# SparkFun_ZOE-M8Q_GPS.net
KiCad netlist of a schematic drawn in EAGLE
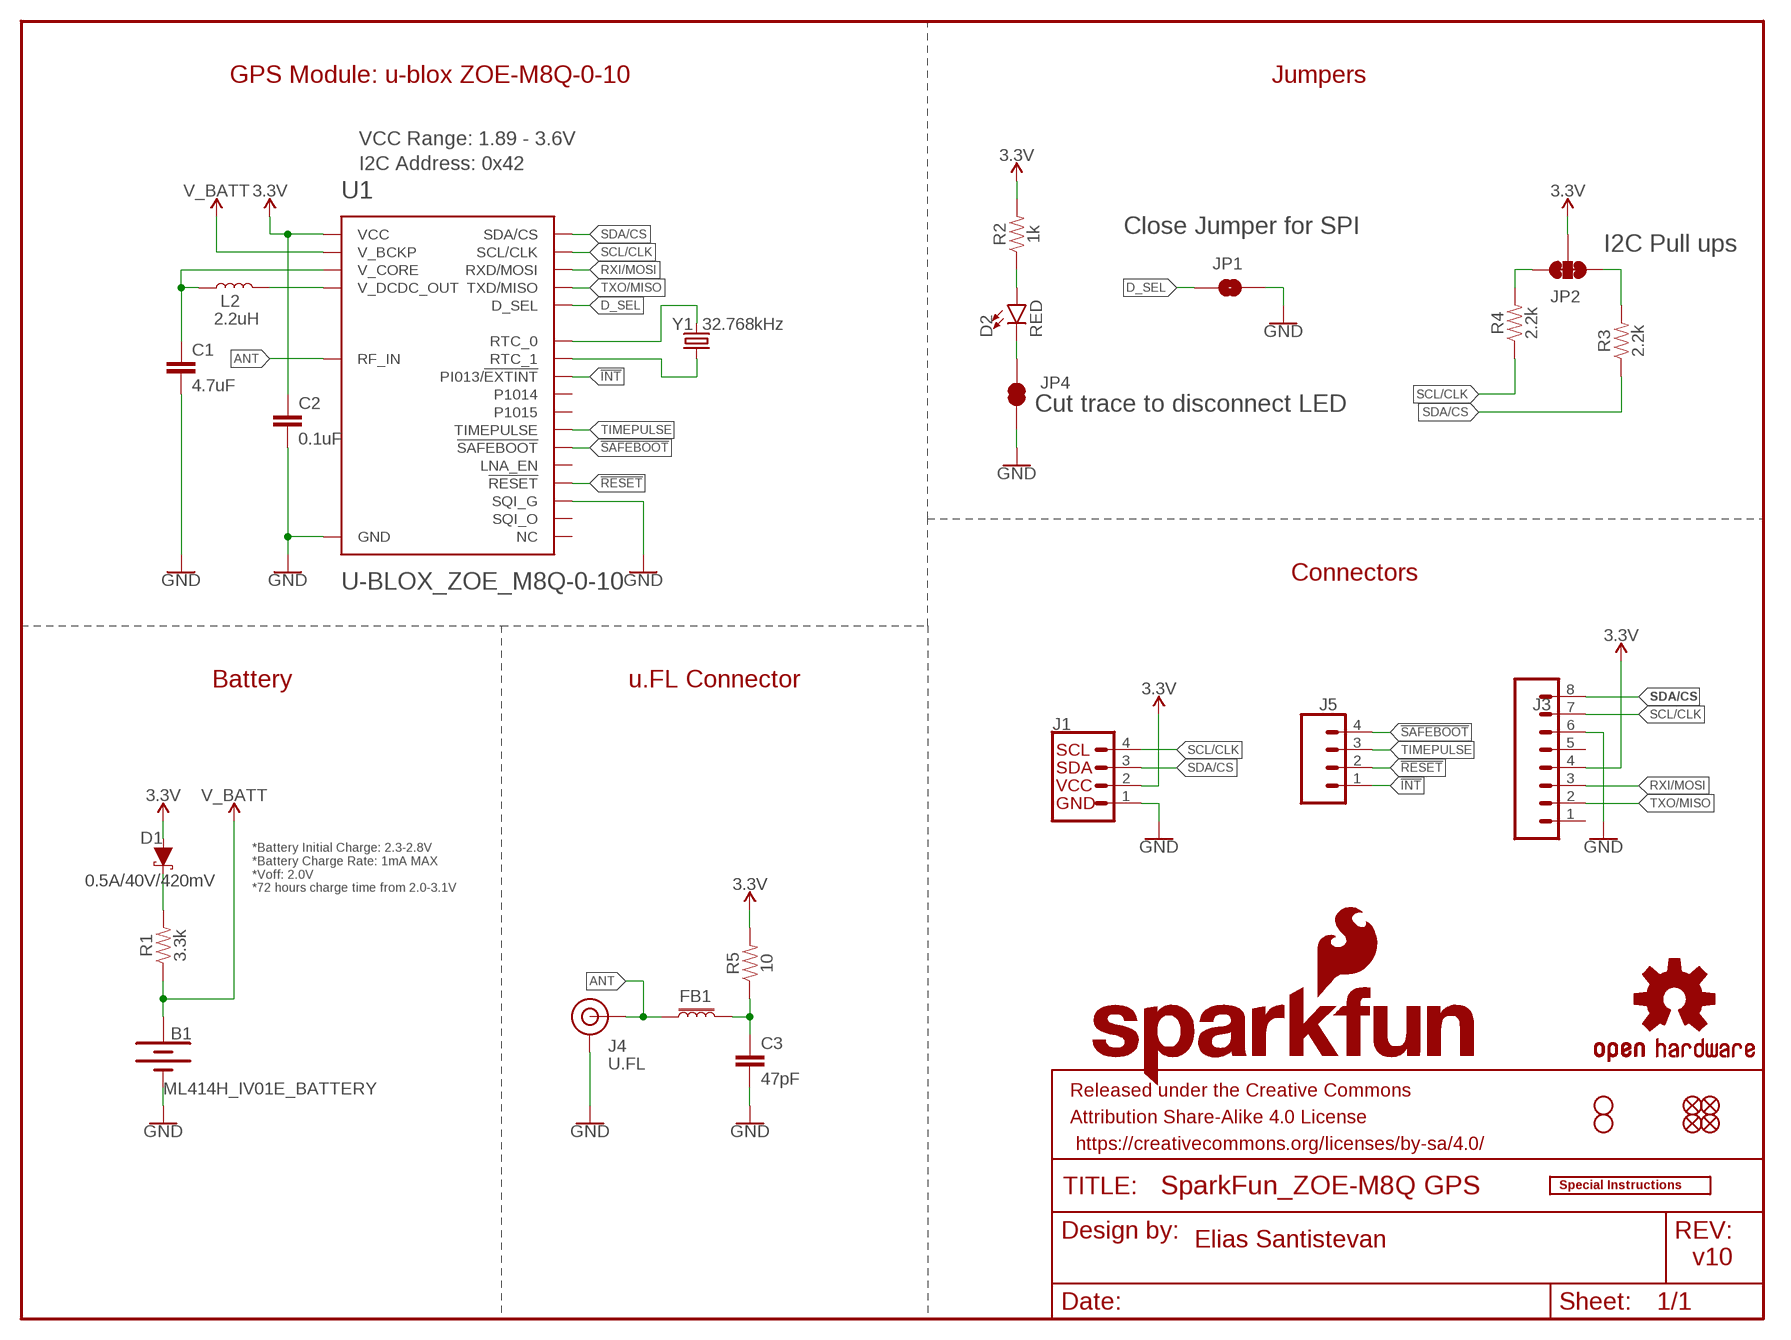
[diagram p0: schematic, sheet 1]

(export (version "E")
  (design (tool "Eeschema 10.0.6"))
  (components
    (comp (ref "B1")
      (value "ML414H_IV01E_BATTERY")
      (footprint "eagle-import:ML414H_IV01E")
      (libsource (lib "eagle-import") (part "ML414H_IV01E_BATTERY"))
    )
    (comp (ref "C1")
      (value "4.7uF")
      (footprint "eagle-import:0603")
      (libsource (lib "eagle-import") (part "4.7UF-0603-6.3V-(10%)"))
    )
    (comp (ref "C2")
      (value "0.1uF")
      (footprint "eagle-import:0603")
      (libsource (lib "eagle-import") (part "0.1UF-0603-25V-(+80/-20%)"))
    )
    (comp (ref "C3")
      (value "47pF")
      (footprint "eagle-import:0603")
      (libsource (lib "eagle-import") (part "47PF-0603-50V-5%"))
    )
    (comp (ref "D1")
      (value "0.5A/40V/420mV")
      (footprint "eagle-import:SOD-323")
      (libsource (lib "eagle-import") (part "DIODE-SCHOTTKY-PMEG4005EJ"))
    )
    (comp (ref "D2")
      (value "RED")
      (footprint "eagle-import:LED-0603")
      (libsource (lib "eagle-import") (part "LED-RED0603"))
    )
    (comp (ref "FB1")
      (value "FERRITE_BEAD-120_OHM-0402")
      (footprint "eagle-import:0402")
      (fields (field (name "MFG_PART") "BLM15HB121SN1D"))
      (libsource (lib "eagle-import") (part "FERRITE_BEAD-120_OHM-0402"))
    )
    (comp (ref "FD1")
      (value "FIDUCIALUFIDUCIAL")
      (footprint "eagle-import:FIDUCIAL-MICRO")
      (libsource (lib "eagle-import") (part "FIDUCIALUFIDUCIAL"))
    )
    (comp (ref "FD2")
      (value "FIDUCIALUFIDUCIAL")
      (footprint "eagle-import:FIDUCIAL-MICRO")
      (libsource (lib "eagle-import") (part "FIDUCIALUFIDUCIAL"))
    )
    (comp (ref "FD3")
      (value "FIDUCIALUFIDUCIAL")
      (footprint "eagle-import:FIDUCIAL-MICRO")
      (libsource (lib "eagle-import") (part "FIDUCIALUFIDUCIAL"))
    )
    (comp (ref "FD4")
      (value "FIDUCIALUFIDUCIAL")
      (footprint "eagle-import:FIDUCIAL-MICRO")
      (libsource (lib "eagle-import") (part "FIDUCIALUFIDUCIAL"))
    )
    (comp (ref "FRAME1")
      (value "FRAME-LETTER")
      (footprint "eagle-import:CREATIVE_COMMONS")
      (libsource (lib "eagle-import") (part "FRAME-LETTER"))
    )
    (comp (ref "H2")
      (value "STAND-OFFTIGHT")
      (footprint "eagle-import:STAND-OFF-TIGHT")
      (libsource (lib "eagle-import") (part "STAND-OFFTIGHT"))
    )
    (comp (ref "H3")
      (value "STAND-OFFTIGHT")
      (footprint "eagle-import:STAND-OFF-TIGHT")
      (libsource (lib "eagle-import") (part "STAND-OFFTIGHT"))
    )
    (comp (ref "J1")
      (value "QWIIC_CONNECTORJS-1MM")
      (footprint "eagle-import:JST04_1MM_RA")
      (libsource (lib "eagle-import") (part "QWIIC_CONNECTORJS-1MM"))
    )
    (comp (ref "J3")
      (value "CONN_08NO_SILK_FEMALE_PTH")
      (footprint "eagle-import:1X08_NO_SILK")
      (libsource (lib "eagle-import") (part "CONN_08NO_SILK_FEMALE_PTH"))
    )
    (comp (ref "J4")
      (value "U.FL")
      (footprint "eagle-import:U.FL")
      (libsource (lib "eagle-import") (part "U.FL2PIN"))
    )
    (comp (ref "J5")
      (value "CONN_041X04_NO_SILK")
      (footprint "eagle-import:1X04_NO_SILK")
      (libsource (lib "eagle-import") (part "CONN_041X04_NO_SILK"))
    )
    (comp (ref "JP1")
      (value "JUMPER-SMT_2_NO_SILK")
      (footprint "eagle-import:SMT-JUMPER_2_NO_SILK")
      (libsource (lib "eagle-import") (part "JUMPER-SMT_2_NO_SILK"))
    )
    (comp (ref "JP2")
      (value "JUMPER-SMT_3_2-NC_TRACE_SILK")
      (footprint "eagle-import:SMT-JUMPER_3_2-NC_TRACE_SILK")
      (libsource (lib "eagle-import") (part "JUMPER-SMT_3_2-NC_TRACE_SILK"))
    )
    (comp (ref "JP4")
      (value "JUMPER-SMT_2_NC_TRACE_SILK")
      (footprint "eagle-import:SMT-JUMPER_2_NC_TRACE_SILK")
      (libsource (lib "eagle-import") (part "JUMPER-SMT_2_NC_TRACE_SILK"))
    )
    (comp (ref "L2")
      (value "2.2uH")
      (footprint "eagle-import:0806")
      (libsource (lib "eagle-import") (part "2.2μH_SHIELDED_INDUCTOR"))
    )
    (comp (ref "LOGO1")
      (value "SFE_LOGO_NAME_FLAME.1_INCH")
      (footprint "eagle-import:SFE_LOGO_NAME_FLAME_.1")
      (libsource (lib "eagle-import") (part "SFE_LOGO_NAME_FLAME.1_INCH"))
    )
    (comp (ref "LOGO2")
      (value "OSHW-LOGOS")
      (footprint "eagle-import:OSHW-LOGO-S")
      (libsource (lib "eagle-import") (part "OSHW-LOGOS"))
    )
    (comp (ref "LOGO3")
      (value "SFE_LOGO_FLAME.1_INCH")
      (footprint "eagle-import:SFE_LOGO_FLAME_.1")
      (libsource (lib "eagle-import") (part "SFE_LOGO_FLAME.1_INCH"))
    )
    (comp (ref "LOGO4")
      (value "SPECIAL_INSTRUCTIONS-ORDERING")
      (footprint "eagle-import:ORDERING_INSTRUCTIONS")
      (libsource (lib "eagle-import") (part "SPECIAL_INSTRUCTIONS-ORDERING"))
    )
    (comp (ref "R1")
      (value "3.3k")
      (footprint "eagle-import:0603")
      (libsource (lib "eagle-import") (part "3.3KOHM-0603-1/10W-1%"))
    )
    (comp (ref "R2")
      (value "1k")
      (footprint "eagle-import:0603")
      (libsource (lib "eagle-import") (part "1KOHM-0603-1/10W-1%"))
    )
    (comp (ref "R3")
      (value "2.2k")
      (footprint "eagle-import:0603")
      (libsource (lib "eagle-import") (part "2.2KOHM-0603-1/10W-1%"))
    )
    (comp (ref "R4")
      (value "2.2k")
      (footprint "eagle-import:0603")
      (libsource (lib "eagle-import") (part "2.2KOHM-0603-1/10W-1%"))
    )
    (comp (ref "R5")
      (value "10")
      (footprint "eagle-import:0603")
      (libsource (lib "eagle-import") (part "10OHM-0603-1/10W-1%"))
    )
    (comp (ref "U1")
      (value "U-BLOX_ZOE_M8Q-0-10")
      (footprint "eagle-import:UBLOX_ZOE_M8-0-10")
      (libsource (lib "eagle-import") (part "U-BLOX_ZOE_M8Q-0-10"))
    )
    (comp (ref "Y1")
      (value "32.768kHz")
      (footprint "eagle-import:CRYSTAL-SMD-3.2X1.5MM")
      (libsource (lib "eagle-import") (part "CRYSTAL-32.768KHZSMD-3.2X1.5"))
    )
  )
  (nets
    (net (code "1") (name "/~{INT}") (class "Default")
      (node (ref "J5") (pin "1") (pinfunction "1_1") (pintype "passive"))
      (node (ref "U1") (pin "43") (pinfunction "PI013/~{EXTINT}_43") (pintype "bidirectional"))
    )
    (net (code "2") (name "/~{RESET}") (class "Default")
      (node (ref "J5") (pin "2") (pinfunction "2_2") (pintype "passive"))
      (node (ref "U1") (pin "20") (pinfunction "~{RESET}_20") (pintype "bidirectional"))
    )
    (net (code "3") (name "/~{SAFEBOOT}") (class "Default")
      (node (ref "J5") (pin "4") (pinfunction "4_4") (pintype "passive"))
      (node (ref "U1") (pin "34") (pinfunction "~{SAFEBOOT}_34") (pintype "bidirectional"))
    )
    (net (code "4") (name "3.3V") (class "Default")
      (node (ref "C2") (pin "1") (pinfunction "1_1") (pintype "passive"))
      (node (ref "D1") (pin "A") (pinfunction "A_A") (pintype "passive"))
      (node (ref "J1") (pin "2") (pinfunction "2_2") (pintype "power_in"))
      (node (ref "J3") (pin "4") (pinfunction "4_4") (pintype "passive"))
      (node (ref "JP2") (pin "2") (pinfunction "2_2") (pintype "passive"))
      (node (ref "R2") (pin "2") (pinfunction "2_2") (pintype "passive"))
      (node (ref "R5") (pin "2") (pinfunction "2_2") (pintype "passive"))
      (node (ref "U1") (pin "24") (pinfunction "VCC_24") (pintype "power_in"))
      (node (ref "U1") (pin "25") (pinfunction "VCC_25") (pintype "power_in"))
    )
    (net (code "5") (name "ANT") (class "Default")
      (node (ref "FB1") (pin "1") (pinfunction "1_1") (pintype "passive"))
      (node (ref "J4") (pin "FEED") (pinfunction "SIGNAL_FEED") (pintype "bidirectional"))
      (node (ref "U1") (pin "4") (pinfunction "RF_IN_4") (pintype "bidirectional"))
    )
    (net (code "6") (name "D_SEL") (class "Default")
      (node (ref "JP1") (pin "1") (pinfunction "1_1") (pintype "passive"))
      (node (ref "U1") (pin "48") (pinfunction "D_SEL_48") (pintype "bidirectional"))
    )
    (net (code "7") (name "GND") (class "Default")
      (node (ref "B1") (pin "-") (pinfunction "-_-") (pintype "power_in"))
      (node (ref "C1") (pin "2") (pinfunction "2_2") (pintype "passive"))
      (node (ref "C2") (pin "2") (pinfunction "2_2") (pintype "passive"))
      (node (ref "C3") (pin "2") (pinfunction "2_2") (pintype "passive"))
      (node (ref "J1") (pin "1") (pinfunction "1_1") (pintype "power_in"))
      (node (ref "J3") (pin "6") (pinfunction "6_6") (pintype "passive"))
      (node (ref "J4") (pin "1") (pinfunction "GND_1") (pintype "bidirectional"))
      (node (ref "J4") (pin "2") (pinfunction "GND_2") (pintype "bidirectional"))
      (node (ref "JP1") (pin "2") (pinfunction "2_2") (pintype "passive"))
      (node (ref "JP4") (pin "1") (pinfunction "1_1") (pintype "passive"))
      (node (ref "U1") (pin "1") (pinfunction "GND_1") (pintype "power_in"))
      (node (ref "U1") (pin "10") (pinfunction "GND_10") (pintype "power_in"))
      (node (ref "U1") (pin "11") (pinfunction "GND_11") (pintype "power_in"))
      (node (ref "U1") (pin "12") (pinfunction "GND_12") (pintype "power_in"))
      (node (ref "U1") (pin "17") (pinfunction "GND_17") (pintype "power_in"))
      (node (ref "U1") (pin "23") (pinfunction "GND_23") (pintype "power_in"))
      (node (ref "U1") (pin "29") (pinfunction "SQI_G_29") (pintype "bidirectional"))
      (node (ref "U1") (pin "3") (pinfunction "GND_3") (pintype "power_in"))
      (node (ref "U1") (pin "31") (pinfunction "SQI_G_31") (pintype "bidirectional"))
      (node (ref "U1") (pin "37") (pinfunction "GND_37") (pintype "power_in"))
      (node (ref "U1") (pin "38") (pinfunction "GND_38") (pintype "power_in"))
      (node (ref "U1") (pin "39") (pinfunction "GND_39") (pintype "power_in"))
      (node (ref "U1") (pin "40") (pinfunction "GND_40") (pintype "power_in"))
      (node (ref "U1") (pin "41") (pinfunction "GND_41") (pintype "power_in"))
      (node (ref "U1") (pin "44") (pinfunction "GND_44") (pintype "power_in"))
      (node (ref "U1") (pin "46") (pinfunction "SQI_G_46") (pintype "bidirectional"))
      (node (ref "U1") (pin "47") (pinfunction "SQI_G_47") (pintype "bidirectional"))
      (node (ref "U1") (pin "49") (pinfunction "GND_49") (pintype "power_in"))
      (node (ref "U1") (pin "5") (pinfunction "GND_5") (pintype "power_in"))
      (node (ref "U1") (pin "7") (pinfunction "GND_7") (pintype "power_in"))
      (node (ref "U1") (pin "8") (pinfunction "GND_8") (pintype "power_in"))
      (node (ref "U1") (pin "9") (pinfunction "GND_9") (pintype "power_in"))
    )
    (net (code "8") (name "Net-(C3-Pad1)") (class "Default")
      (node (ref "C3") (pin "1") (pinfunction "1_1") (pintype "passive"))
      (node (ref "FB1") (pin "2") (pinfunction "2_2") (pintype "passive"))
      (node (ref "R5") (pin "1") (pinfunction "1_1") (pintype "passive"))
    )
    (net (code "9") (name "Net-(D1-PadC)") (class "Default")
      (node (ref "D1") (pin "C") (pinfunction "C_C") (pintype "passive"))
      (node (ref "R1") (pin "2") (pinfunction "2_2") (pintype "passive"))
    )
    (net (code "10") (name "Net-(D2-PadA)") (class "Default")
      (node (ref "D2") (pin "A") (pinfunction "A_A") (pintype "passive"))
      (node (ref "R2") (pin "1") (pinfunction "1_1") (pintype "passive"))
    )
    (net (code "11") (name "Net-(D2-PadC)") (class "Default")
      (node (ref "D2") (pin "C") (pinfunction "C_C") (pintype "passive"))
      (node (ref "JP4") (pin "2") (pinfunction "2_2") (pintype "passive"))
    )
    (net (code "12") (name "Net-(JP2-Pad1)") (class "Default")
      (node (ref "JP2") (pin "1") (pinfunction "1_1") (pintype "passive"))
      (node (ref "R3") (pin "2") (pinfunction "2_2") (pintype "passive"))
    )
    (net (code "13") (name "Net-(JP2-Pad3)") (class "Default")
      (node (ref "JP2") (pin "3") (pinfunction "3_3") (pintype "passive"))
      (node (ref "R4") (pin "2") (pinfunction "2_2") (pintype "passive"))
    )
    (net (code "14") (name "Net-(U1-RTC_0)") (class "Default")
      (node (ref "U1") (pin "18") (pinfunction "RTC_0_18") (pintype "bidirectional"))
      (node (ref "Y1") (pin "P$2") (pinfunction "2_P$2") (pintype "passive"))
    )
    (net (code "15") (name "Net-(U1-RTC_1)") (class "Default")
      (node (ref "U1") (pin "19") (pinfunction "RTC_1_19") (pintype "bidirectional"))
      (node (ref "Y1") (pin "P$1") (pinfunction "1_P$1") (pintype "passive"))
    )
    (net (code "16") (name "Net-(U1-V_CORE)") (class "Default")
      (node (ref "C1") (pin "1") (pinfunction "1_1") (pintype "passive"))
      (node (ref "L2") (pin "1") (pinfunction "1_1") (pintype "passive"))
      (node (ref "U1") (pin "27") (pinfunction "V_CORE_27") (pintype "power_in"))
    )
    (net (code "17") (name "Net-(U1-V_DCDC_OUT)") (class "Default")
      (node (ref "L2") (pin "2") (pinfunction "2_2") (pintype "passive"))
      (node (ref "U1") (pin "26") (pinfunction "V_DCDC_OUT_26") (pintype "power_in"))
    )
    (net (code "18") (name "RXI{slash}MOSI") (class "Default")
      (node (ref "J3") (pin "3") (pinfunction "3_3") (pintype "passive"))
      (node (ref "U1") (pin "22") (pinfunction "RXD/MOSI_22") (pintype "bidirectional"))
    )
    (net (code "19") (name "SCL{slash}CLK") (class "Default")
      (node (ref "J1") (pin "4") (pinfunction "4_4") (pintype "passive"))
      (node (ref "J3") (pin "7") (pinfunction "7_7") (pintype "passive"))
      (node (ref "R4") (pin "1") (pinfunction "1_1") (pintype "passive"))
      (node (ref "U1") (pin "32") (pinfunction "SCL/CLK_32") (pintype "bidirectional"))
    )
    (net (code "20") (name "SDA{slash}CS") (class "Default")
      (node (ref "J1") (pin "3") (pinfunction "3_3") (pintype "passive"))
      (node (ref "J3") (pin "8") (pinfunction "8_8") (pintype "passive"))
      (node (ref "R3") (pin "1") (pinfunction "1_1") (pintype "passive"))
      (node (ref "U1") (pin "2") (pinfunction "SDA/CS_2") (pintype "bidirectional"))
    )
    (net (code "21") (name "TIMEPULSE") (class "Default")
      (node (ref "J5") (pin "3") (pinfunction "3_3") (pintype "passive"))
      (node (ref "U1") (pin "33") (pinfunction "TIMEPULSE_33") (pintype "bidirectional"))
    )
    (net (code "22") (name "TXO{slash}MISO") (class "Default")
      (node (ref "J3") (pin "2") (pinfunction "2_2") (pintype "passive"))
      (node (ref "U1") (pin "21") (pinfunction "TXD/MISO_21") (pintype "bidirectional"))
    )
    (net (code "23") (name "V_BATT") (class "Default")
      (node (ref "B1") (pin "+") (pinfunction "+_+") (pintype "power_in"))
      (node (ref "R1") (pin "1") (pinfunction "1_1") (pintype "passive"))
      (node (ref "U1") (pin "16") (pinfunction "V_BCKP_16") (pintype "power_in"))
    )
    (net (code "24") (name "unconnected-(J3-Pad1)") (class "Default")
      (node (ref "J3") (pin "1") (pinfunction "1_1") (pintype "passive"))
    )
    (net (code "25") (name "unconnected-(J3-Pad5)") (class "Default")
      (node (ref "J3") (pin "5") (pinfunction "5_5") (pintype "passive"))
    )
    (net (code "26") (name "unconnected-(U1-LNA_EN-Pad35)") (class "Default")
      (node (ref "U1") (pin "35") (pinfunction "LNA_EN_35") (pintype "bidirectional"))
    )
    (net (code "27") (name "unconnected-(U1-NC-Pad6)") (class "Default")
      (node (ref "U1") (pin "6") (pinfunction "NC_6") (pintype "no_connect"))
    )
    (net (code "28") (name "unconnected-(U1-NC-Pad13)") (class "Default")
      (node (ref "U1") (pin "13") (pinfunction "NC_13") (pintype "no_connect"))
    )
    (net (code "29") (name "unconnected-(U1-NC-Pad14)") (class "Default")
      (node (ref "U1") (pin "14") (pinfunction "NC_14") (pintype "no_connect"))
    )
    (net (code "30") (name "unconnected-(U1-NC-Pad15)") (class "Default")
      (node (ref "U1") (pin "15") (pinfunction "NC_15") (pintype "no_connect"))
    )
    (net (code "31") (name "unconnected-(U1-NC-Pad28)") (class "Default")
      (node (ref "U1") (pin "28") (pinfunction "NC_28") (pintype "no_connect"))
    )
    (net (code "32") (name "unconnected-(U1-NC-Pad42)") (class "Default")
      (node (ref "U1") (pin "42") (pinfunction "NC_42") (pintype "no_connect"))
    )
    (net (code "33") (name "unconnected-(U1-NC-Pad51)") (class "Default")
      (node (ref "U1") (pin "51") (pinfunction "NC_51") (pintype "no_connect"))
    )
    (net (code "34") (name "unconnected-(U1-P1014-Pad50)") (class "Default")
      (node (ref "U1") (pin "50") (pinfunction "P1014_50") (pintype "bidirectional"))
    )
    (net (code "35") (name "unconnected-(U1-P1015-Pad36)") (class "Default")
      (node (ref "U1") (pin "36") (pinfunction "P1015_36") (pintype "bidirectional"))
    )
    (net (code "36") (name "unconnected-(U1-SQI_O-Pad30)") (class "Default")
      (node (ref "U1") (pin "30") (pinfunction "SQI_O_30") (pintype "no_connect"))
    )
    (net (code "37") (name "unconnected-(U1-SQI_O-Pad45)") (class "Default")
      (node (ref "U1") (pin "45") (pinfunction "SQI_O_45") (pintype "no_connect"))
    )
  )
)
